# BUS_SPLIT_DISPLAY_1.net
KiCad netlist of a schematic drawn in EAGLE
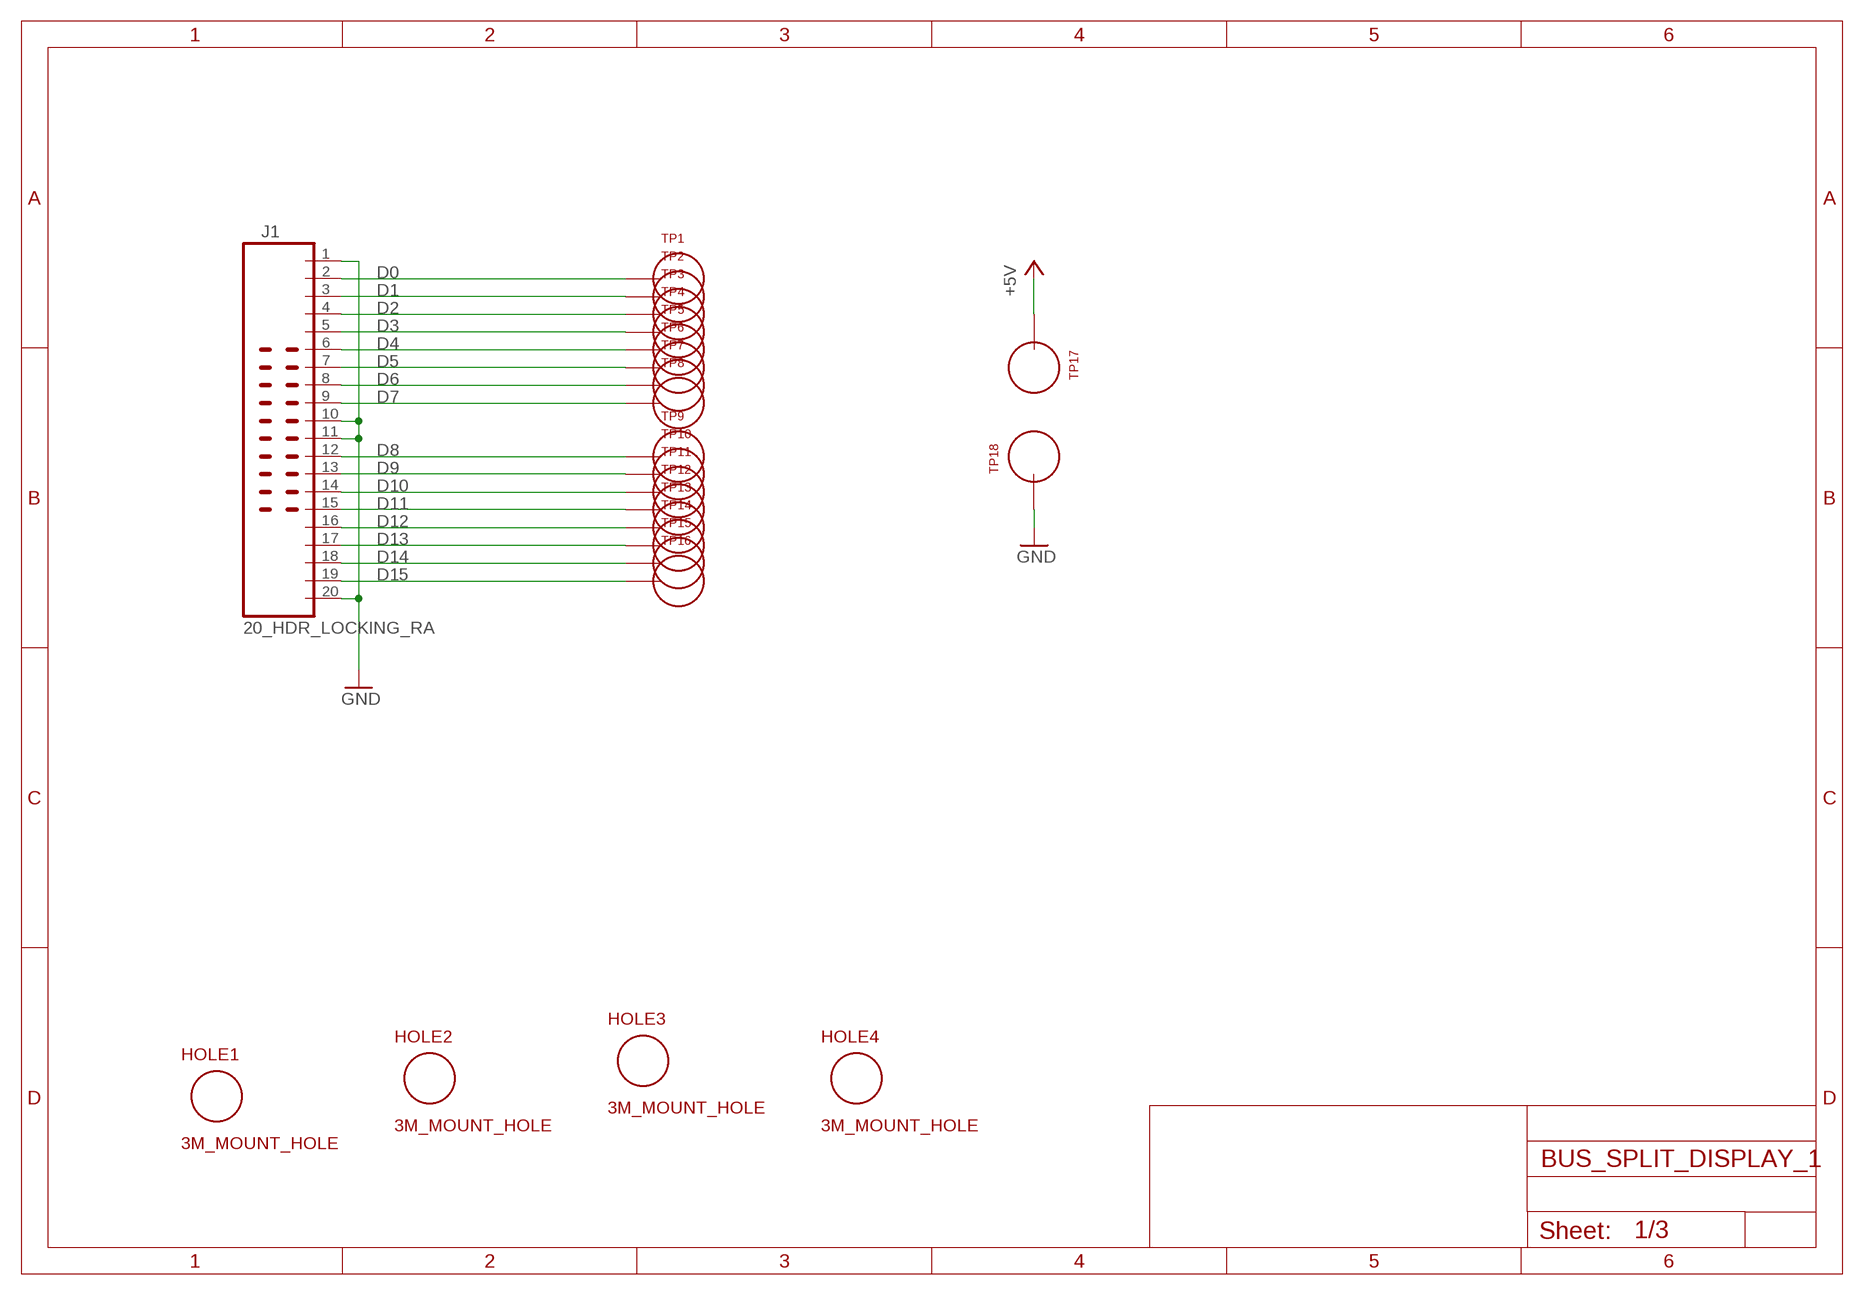
[diagram p0: schematic, sheet 1]
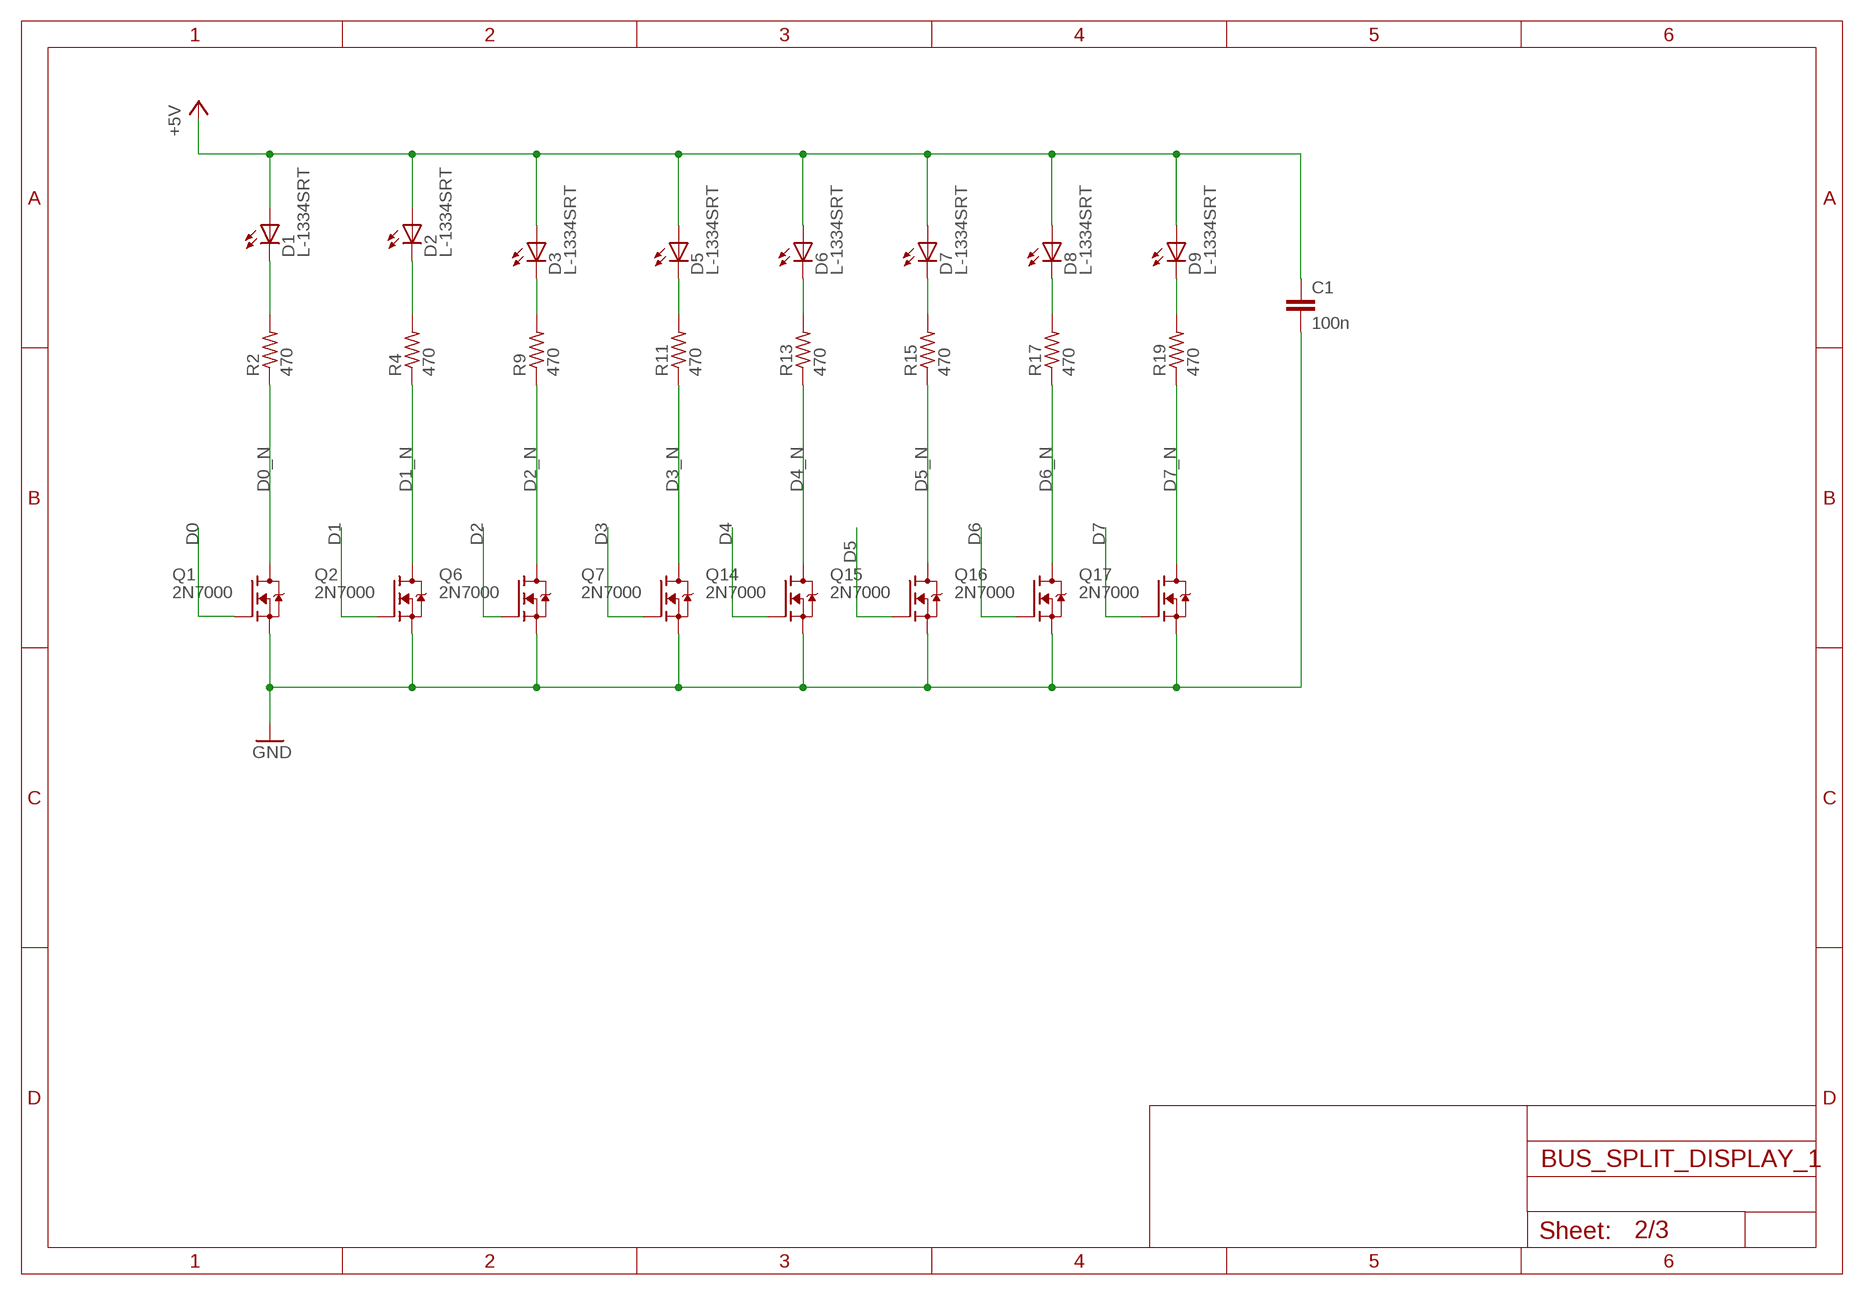
[diagram p1: schematic, sheet 2]
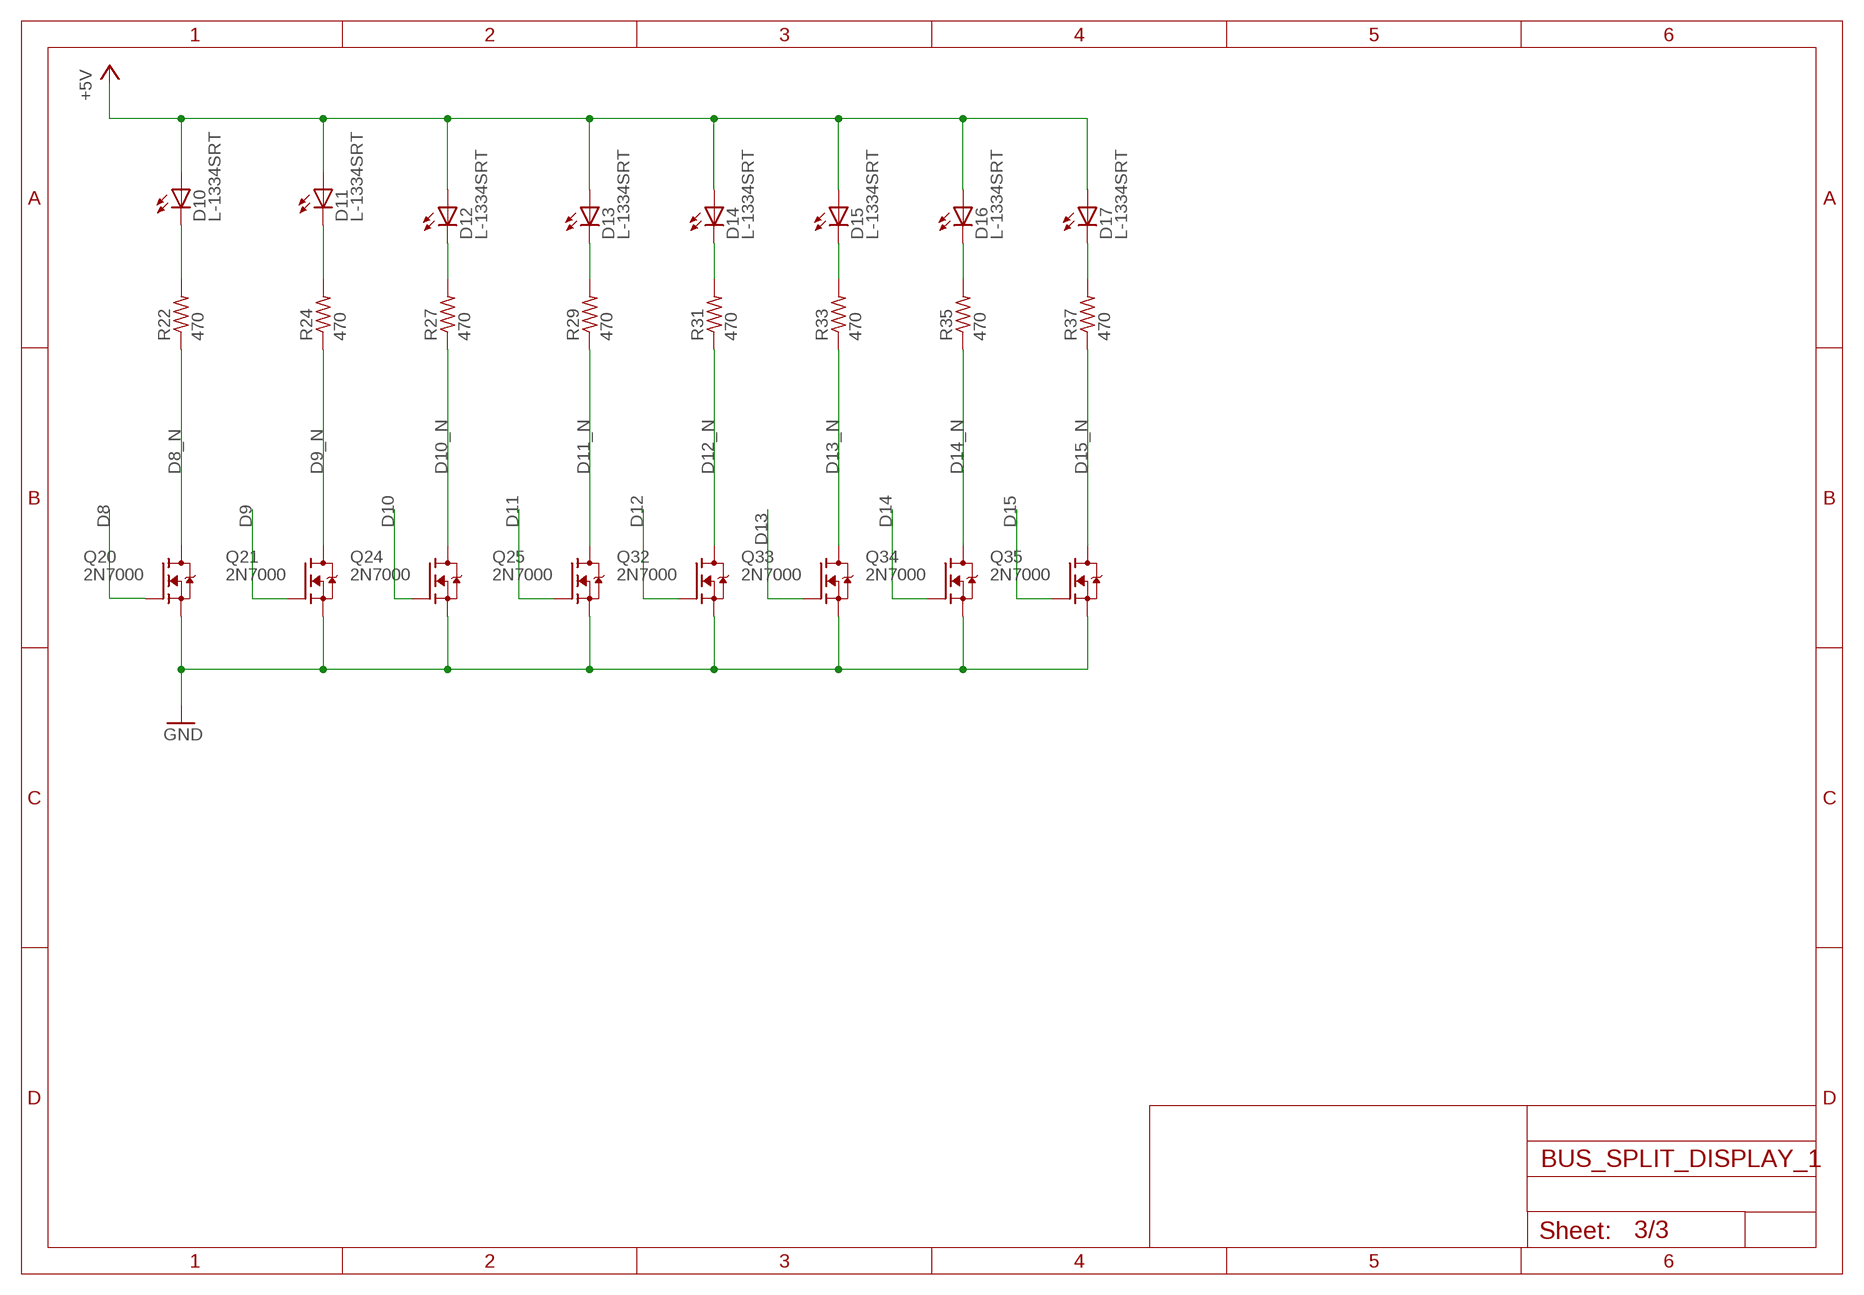
[diagram p2: schematic, sheet 3]

(export (version "E")
  (design (tool "Eeschema 10.0.6"))
  (components
    (comp (ref "D10")
      (value "L-1334SRT")
      (footprint "eagle-import:LED3MM")
      (libsource (lib "eagle-import") (part "L-1334SRT"))
    )
    (comp (ref "D11")
      (value "L-1334SRT")
      (footprint "eagle-import:LED3MM")
      (libsource (lib "eagle-import") (part "L-1334SRT"))
    )
    (comp (ref "D12")
      (value "L-1334SRT")
      (footprint "eagle-import:LED3MM")
      (libsource (lib "eagle-import") (part "L-1334SRT"))
    )
    (comp (ref "D13")
      (value "L-1334SRT")
      (footprint "eagle-import:LED3MM")
      (libsource (lib "eagle-import") (part "L-1334SRT"))
    )
    (comp (ref "D14")
      (value "L-1334SRT")
      (footprint "eagle-import:LED3MM")
      (libsource (lib "eagle-import") (part "L-1334SRT"))
    )
    (comp (ref "D15")
      (value "L-1334SRT")
      (footprint "eagle-import:LED3MM")
      (libsource (lib "eagle-import") (part "L-1334SRT"))
    )
    (comp (ref "D16")
      (value "L-1334SRT")
      (footprint "eagle-import:LED3MM")
      (libsource (lib "eagle-import") (part "L-1334SRT"))
    )
    (comp (ref "D17")
      (value "L-1334SRT")
      (footprint "eagle-import:LED3MM")
      (libsource (lib "eagle-import") (part "L-1334SRT"))
    )
    (comp (ref "Q20")
      (value "2N7000")
      (footprint "eagle-import:TO92-DGS")
      (libsource (lib "eagle-import") (part "2N7000"))
    )
    (comp (ref "Q21")
      (value "2N7000")
      (footprint "eagle-import:TO92-DGS")
      (libsource (lib "eagle-import") (part "2N7000"))
    )
    (comp (ref "Q24")
      (value "2N7000")
      (footprint "eagle-import:TO92-DGS")
      (libsource (lib "eagle-import") (part "2N7000"))
    )
    (comp (ref "Q25")
      (value "2N7000")
      (footprint "eagle-import:TO92-DGS")
      (libsource (lib "eagle-import") (part "2N7000"))
    )
    (comp (ref "Q32")
      (value "2N7000")
      (footprint "eagle-import:TO92-DGS")
      (libsource (lib "eagle-import") (part "2N7000"))
    )
    (comp (ref "Q33")
      (value "2N7000")
      (footprint "eagle-import:TO92-DGS")
      (libsource (lib "eagle-import") (part "2N7000"))
    )
    (comp (ref "Q34")
      (value "2N7000")
      (footprint "eagle-import:TO92-DGS")
      (libsource (lib "eagle-import") (part "2N7000"))
    )
    (comp (ref "Q35")
      (value "2N7000")
      (footprint "eagle-import:TO92-DGS")
      (libsource (lib "eagle-import") (part "2N7000"))
    )
    (comp (ref "R22")
      (value "470")
      (footprint "eagle-import:R_P2INCH")
      (libsource (lib "eagle-import") (part "R_P2INCH"))
    )
    (comp (ref "R24")
      (value "470")
      (footprint "eagle-import:R_P2INCH")
      (libsource (lib "eagle-import") (part "R_P2INCH"))
    )
    (comp (ref "R27")
      (value "470")
      (footprint "eagle-import:R_P2INCH")
      (libsource (lib "eagle-import") (part "R_P2INCH"))
    )
    (comp (ref "R29")
      (value "470")
      (footprint "eagle-import:R_P2INCH")
      (libsource (lib "eagle-import") (part "R_P2INCH"))
    )
    (comp (ref "R31")
      (value "470")
      (footprint "eagle-import:R_P2INCH")
      (libsource (lib "eagle-import") (part "R_P2INCH"))
    )
    (comp (ref "R33")
      (value "470")
      (footprint "eagle-import:R_P2INCH")
      (libsource (lib "eagle-import") (part "R_P2INCH"))
    )
    (comp (ref "R35")
      (value "470")
      (footprint "eagle-import:R_P2INCH")
      (libsource (lib "eagle-import") (part "R_P2INCH"))
    )
    (comp (ref "R37")
      (value "470")
      (footprint "eagle-import:R_P2INCH")
      (libsource (lib "eagle-import") (part "R_P2INCH"))
    )
    (comp (ref "HOLE1")
      (value "3M_MOUNT_HOLE")
      (footprint "eagle-import:3M_HOLE")
      (libsource (lib "eagle-import") (part "3M_MOUNT_HOLE"))
    )
    (comp (ref "HOLE2")
      (value "3M_MOUNT_HOLE")
      (footprint "eagle-import:3M_HOLE")
      (libsource (lib "eagle-import") (part "3M_MOUNT_HOLE"))
    )
    (comp (ref "HOLE3")
      (value "3M_MOUNT_HOLE")
      (footprint "eagle-import:3M_HOLE")
      (libsource (lib "eagle-import") (part "3M_MOUNT_HOLE"))
    )
    (comp (ref "HOLE4")
      (value "3M_MOUNT_HOLE")
      (footprint "eagle-import:3M_HOLE")
      (libsource (lib "eagle-import") (part "3M_MOUNT_HOLE"))
    )
    (comp (ref "J1")
      (value "20_HDR_LOCKING_RA")
      (footprint "eagle-import:20_HDR_LOCKING_RA")
      (libsource (lib "eagle-import") (part "20_HDR_LOCKING_RA"))
    )
    (comp (ref "TP1")
      (value "TEST_LOOP")
      (footprint "eagle-import:TEST_LOOP")
      (libsource (lib "eagle-import") (part "TEST_LOOP"))
    )
    (comp (ref "TP2")
      (value "TEST_LOOP")
      (footprint "eagle-import:TEST_LOOP")
      (libsource (lib "eagle-import") (part "TEST_LOOP"))
    )
    (comp (ref "TP3")
      (value "TEST_LOOP")
      (footprint "eagle-import:TEST_LOOP")
      (libsource (lib "eagle-import") (part "TEST_LOOP"))
    )
    (comp (ref "TP4")
      (value "TEST_LOOP")
      (footprint "eagle-import:TEST_LOOP")
      (libsource (lib "eagle-import") (part "TEST_LOOP"))
    )
    (comp (ref "TP5")
      (value "TEST_LOOP")
      (footprint "eagle-import:TEST_LOOP")
      (libsource (lib "eagle-import") (part "TEST_LOOP"))
    )
    (comp (ref "TP6")
      (value "TEST_LOOP")
      (footprint "eagle-import:TEST_LOOP")
      (libsource (lib "eagle-import") (part "TEST_LOOP"))
    )
    (comp (ref "TP7")
      (value "TEST_LOOP")
      (footprint "eagle-import:TEST_LOOP")
      (libsource (lib "eagle-import") (part "TEST_LOOP"))
    )
    (comp (ref "TP8")
      (value "TEST_LOOP")
      (footprint "eagle-import:TEST_LOOP")
      (libsource (lib "eagle-import") (part "TEST_LOOP"))
    )
    (comp (ref "TP9")
      (value "TEST_LOOP")
      (footprint "eagle-import:TEST_LOOP")
      (libsource (lib "eagle-import") (part "TEST_LOOP"))
    )
    (comp (ref "TP10")
      (value "TEST_LOOP")
      (footprint "eagle-import:TEST_LOOP")
      (libsource (lib "eagle-import") (part "TEST_LOOP"))
    )
    (comp (ref "TP11")
      (value "TEST_LOOP")
      (footprint "eagle-import:TEST_LOOP")
      (libsource (lib "eagle-import") (part "TEST_LOOP"))
    )
    (comp (ref "TP12")
      (value "TEST_LOOP")
      (footprint "eagle-import:TEST_LOOP")
      (libsource (lib "eagle-import") (part "TEST_LOOP"))
    )
    (comp (ref "TP13")
      (value "TEST_LOOP")
      (footprint "eagle-import:TEST_LOOP")
      (libsource (lib "eagle-import") (part "TEST_LOOP"))
    )
    (comp (ref "TP14")
      (value "TEST_LOOP")
      (footprint "eagle-import:TEST_LOOP")
      (libsource (lib "eagle-import") (part "TEST_LOOP"))
    )
    (comp (ref "TP15")
      (value "TEST_LOOP")
      (footprint "eagle-import:TEST_LOOP")
      (libsource (lib "eagle-import") (part "TEST_LOOP"))
    )
    (comp (ref "TP16")
      (value "TEST_LOOP")
      (footprint "eagle-import:TEST_LOOP")
      (libsource (lib "eagle-import") (part "TEST_LOOP"))
    )
    (comp (ref "TP17")
      (value "TEST_LOOP")
      (footprint "eagle-import:TEST_LOOP")
      (libsource (lib "eagle-import") (part "TEST_LOOP"))
    )
    (comp (ref "TP18")
      (value "TEST_LOOP")
      (footprint "eagle-import:TEST_LOOP")
      (libsource (lib "eagle-import") (part "TEST_LOOP"))
    )
    (comp (ref "C1")
      (value "100n")
      (footprint "eagle-import:CAP_P2INCH")
      (libsource (lib "eagle-import") (part "C_P2INCH"))
    )
    (comp (ref "D1")
      (value "L-1334SRT")
      (footprint "eagle-import:LED3MM")
      (libsource (lib "eagle-import") (part "L-1334SRT"))
    )
    (comp (ref "D2")
      (value "L-1334SRT")
      (footprint "eagle-import:LED3MM")
      (libsource (lib "eagle-import") (part "L-1334SRT"))
    )
    (comp (ref "D3")
      (value "L-1334SRT")
      (footprint "eagle-import:LED3MM")
      (libsource (lib "eagle-import") (part "L-1334SRT"))
    )
    (comp (ref "D5")
      (value "L-1334SRT")
      (footprint "eagle-import:LED3MM")
      (libsource (lib "eagle-import") (part "L-1334SRT"))
    )
    (comp (ref "D6")
      (value "L-1334SRT")
      (footprint "eagle-import:LED3MM")
      (libsource (lib "eagle-import") (part "L-1334SRT"))
    )
    (comp (ref "D7")
      (value "L-1334SRT")
      (footprint "eagle-import:LED3MM")
      (libsource (lib "eagle-import") (part "L-1334SRT"))
    )
    (comp (ref "D8")
      (value "L-1334SRT")
      (footprint "eagle-import:LED3MM")
      (libsource (lib "eagle-import") (part "L-1334SRT"))
    )
    (comp (ref "D9")
      (value "L-1334SRT")
      (footprint "eagle-import:LED3MM")
      (libsource (lib "eagle-import") (part "L-1334SRT"))
    )
    (comp (ref "Q1")
      (value "2N7000")
      (footprint "eagle-import:TO92-DGS")
      (libsource (lib "eagle-import") (part "2N7000"))
    )
    (comp (ref "Q2")
      (value "2N7000")
      (footprint "eagle-import:TO92-DGS")
      (libsource (lib "eagle-import") (part "2N7000"))
    )
    (comp (ref "Q6")
      (value "2N7000")
      (footprint "eagle-import:TO92-DGS")
      (libsource (lib "eagle-import") (part "2N7000"))
    )
    (comp (ref "Q7")
      (value "2N7000")
      (footprint "eagle-import:TO92-DGS")
      (libsource (lib "eagle-import") (part "2N7000"))
    )
    (comp (ref "Q14")
      (value "2N7000")
      (footprint "eagle-import:TO92-DGS")
      (libsource (lib "eagle-import") (part "2N7000"))
    )
    (comp (ref "Q15")
      (value "2N7000")
      (footprint "eagle-import:TO92-DGS")
      (libsource (lib "eagle-import") (part "2N7000"))
    )
    (comp (ref "Q16")
      (value "2N7000")
      (footprint "eagle-import:TO92-DGS")
      (libsource (lib "eagle-import") (part "2N7000"))
    )
    (comp (ref "Q17")
      (value "2N7000")
      (footprint "eagle-import:TO92-DGS")
      (libsource (lib "eagle-import") (part "2N7000"))
    )
    (comp (ref "R2")
      (value "470")
      (footprint "eagle-import:R_P2INCH")
      (libsource (lib "eagle-import") (part "R_P2INCH"))
    )
    (comp (ref "R4")
      (value "470")
      (footprint "eagle-import:R_P2INCH")
      (libsource (lib "eagle-import") (part "R_P2INCH"))
    )
    (comp (ref "R9")
      (value "470")
      (footprint "eagle-import:R_P2INCH")
      (libsource (lib "eagle-import") (part "R_P2INCH"))
    )
    (comp (ref "R11")
      (value "470")
      (footprint "eagle-import:R_P2INCH")
      (libsource (lib "eagle-import") (part "R_P2INCH"))
    )
    (comp (ref "R13")
      (value "470")
      (footprint "eagle-import:R_P2INCH")
      (libsource (lib "eagle-import") (part "R_P2INCH"))
    )
    (comp (ref "R15")
      (value "470")
      (footprint "eagle-import:R_P2INCH")
      (libsource (lib "eagle-import") (part "R_P2INCH"))
    )
    (comp (ref "R17")
      (value "470")
      (footprint "eagle-import:R_P2INCH")
      (libsource (lib "eagle-import") (part "R_P2INCH"))
    )
    (comp (ref "R19")
      (value "470")
      (footprint "eagle-import:R_P2INCH")
      (libsource (lib "eagle-import") (part "R_P2INCH"))
    )
  )
  (nets
    (net (code "1") (name "+5V") (class "Default")
      (node (ref "C1") (pin "1") (pinfunction "1_1") (pintype "passive"))
      (node (ref "D1") (pin "A") (pinfunction "A_A") (pintype "passive"))
      (node (ref "D10") (pin "A") (pinfunction "A_A") (pintype "passive"))
      (node (ref "D11") (pin "A") (pinfunction "A_A") (pintype "passive"))
      (node (ref "D12") (pin "A") (pinfunction "A_A") (pintype "passive"))
      (node (ref "D13") (pin "A") (pinfunction "A_A") (pintype "passive"))
      (node (ref "D14") (pin "A") (pinfunction "A_A") (pintype "passive"))
      (node (ref "D15") (pin "A") (pinfunction "A_A") (pintype "passive"))
      (node (ref "D16") (pin "A") (pinfunction "A_A") (pintype "passive"))
      (node (ref "D17") (pin "A") (pinfunction "A_A") (pintype "passive"))
      (node (ref "D2") (pin "A") (pinfunction "A_A") (pintype "passive"))
      (node (ref "D3") (pin "A") (pinfunction "A_A") (pintype "passive"))
      (node (ref "D5") (pin "A") (pinfunction "A_A") (pintype "passive"))
      (node (ref "D6") (pin "A") (pinfunction "A_A") (pintype "passive"))
      (node (ref "D7") (pin "A") (pinfunction "A_A") (pintype "passive"))
      (node (ref "D8") (pin "A") (pinfunction "A_A") (pintype "passive"))
      (node (ref "D9") (pin "A") (pinfunction "A_A") (pintype "passive"))
      (node (ref "TP17") (pin "P$1") (pinfunction "P$1_P$1") (pintype "bidirectional"))
    )
    (net (code "2") (name "D0") (class "Default")
      (node (ref "J1") (pin "2") (pinfunction "2_2") (pintype "bidirectional"))
      (node (ref "Q1") (pin "G") (pinfunction "G_G") (pintype "passive"))
      (node (ref "TP1") (pin "P$1") (pinfunction "P$1_P$1") (pintype "bidirectional"))
    )
    (net (code "3") (name "D0_N") (class "Default")
      (node (ref "Q1") (pin "D") (pinfunction "D_D") (pintype "passive"))
      (node (ref "R2") (pin "1") (pinfunction "1_1") (pintype "passive"))
    )
    (net (code "4") (name "D1") (class "Default")
      (node (ref "J1") (pin "3") (pinfunction "3_3") (pintype "bidirectional"))
      (node (ref "Q2") (pin "G") (pinfunction "G_G") (pintype "passive"))
      (node (ref "TP2") (pin "P$1") (pinfunction "P$1_P$1") (pintype "bidirectional"))
    )
    (net (code "5") (name "D1_N") (class "Default")
      (node (ref "Q2") (pin "D") (pinfunction "D_D") (pintype "passive"))
      (node (ref "R4") (pin "1") (pinfunction "1_1") (pintype "passive"))
    )
    (net (code "6") (name "D2") (class "Default")
      (node (ref "J1") (pin "4") (pinfunction "4_4") (pintype "bidirectional"))
      (node (ref "Q6") (pin "G") (pinfunction "G_G") (pintype "passive"))
      (node (ref "TP3") (pin "P$1") (pinfunction "P$1_P$1") (pintype "bidirectional"))
    )
    (net (code "7") (name "D2_N") (class "Default")
      (node (ref "Q6") (pin "D") (pinfunction "D_D") (pintype "passive"))
      (node (ref "R9") (pin "1") (pinfunction "1_1") (pintype "passive"))
    )
    (net (code "8") (name "D3") (class "Default")
      (node (ref "J1") (pin "5") (pinfunction "5_5") (pintype "bidirectional"))
      (node (ref "Q7") (pin "G") (pinfunction "G_G") (pintype "passive"))
      (node (ref "TP4") (pin "P$1") (pinfunction "P$1_P$1") (pintype "bidirectional"))
    )
    (net (code "9") (name "D3_N") (class "Default")
      (node (ref "Q7") (pin "D") (pinfunction "D_D") (pintype "passive"))
      (node (ref "R11") (pin "1") (pinfunction "1_1") (pintype "passive"))
    )
    (net (code "10") (name "D4") (class "Default")
      (node (ref "J1") (pin "6") (pinfunction "6_6") (pintype "bidirectional"))
      (node (ref "Q14") (pin "G") (pinfunction "G_G") (pintype "passive"))
      (node (ref "TP5") (pin "P$1") (pinfunction "P$1_P$1") (pintype "bidirectional"))
    )
    (net (code "11") (name "D4_N") (class "Default")
      (node (ref "Q14") (pin "D") (pinfunction "D_D") (pintype "passive"))
      (node (ref "R13") (pin "1") (pinfunction "1_1") (pintype "passive"))
    )
    (net (code "12") (name "D5") (class "Default")
      (node (ref "J1") (pin "7") (pinfunction "7_7") (pintype "bidirectional"))
      (node (ref "Q15") (pin "G") (pinfunction "G_G") (pintype "passive"))
      (node (ref "TP6") (pin "P$1") (pinfunction "P$1_P$1") (pintype "bidirectional"))
    )
    (net (code "13") (name "D5_N") (class "Default")
      (node (ref "Q15") (pin "D") (pinfunction "D_D") (pintype "passive"))
      (node (ref "R15") (pin "1") (pinfunction "1_1") (pintype "passive"))
    )
    (net (code "14") (name "D6") (class "Default")
      (node (ref "J1") (pin "8") (pinfunction "8_8") (pintype "bidirectional"))
      (node (ref "Q16") (pin "G") (pinfunction "G_G") (pintype "passive"))
      (node (ref "TP7") (pin "P$1") (pinfunction "P$1_P$1") (pintype "bidirectional"))
    )
    (net (code "15") (name "D6_N") (class "Default")
      (node (ref "Q16") (pin "D") (pinfunction "D_D") (pintype "passive"))
      (node (ref "R17") (pin "1") (pinfunction "1_1") (pintype "passive"))
    )
    (net (code "16") (name "D7") (class "Default")
      (node (ref "J1") (pin "9") (pinfunction "9_9") (pintype "bidirectional"))
      (node (ref "Q17") (pin "G") (pinfunction "G_G") (pintype "passive"))
      (node (ref "TP8") (pin "P$1") (pinfunction "P$1_P$1") (pintype "bidirectional"))
    )
    (net (code "17") (name "D7_N") (class "Default")
      (node (ref "Q17") (pin "D") (pinfunction "D_D") (pintype "passive"))
      (node (ref "R19") (pin "1") (pinfunction "1_1") (pintype "passive"))
    )
    (net (code "18") (name "D8") (class "Default")
      (node (ref "J1") (pin "12") (pinfunction "12_12") (pintype "bidirectional"))
      (node (ref "Q20") (pin "G") (pinfunction "G_G") (pintype "passive"))
      (node (ref "TP9") (pin "P$1") (pinfunction "P$1_P$1") (pintype "bidirectional"))
    )
    (net (code "19") (name "D8_N") (class "Default")
      (node (ref "Q20") (pin "D") (pinfunction "D_D") (pintype "passive"))
      (node (ref "R22") (pin "1") (pinfunction "1_1") (pintype "passive"))
    )
    (net (code "20") (name "D9") (class "Default")
      (node (ref "J1") (pin "13") (pinfunction "13_13") (pintype "bidirectional"))
      (node (ref "Q21") (pin "G") (pinfunction "G_G") (pintype "passive"))
      (node (ref "TP10") (pin "P$1") (pinfunction "P$1_P$1") (pintype "bidirectional"))
    )
    (net (code "21") (name "D9_N") (class "Default")
      (node (ref "Q21") (pin "D") (pinfunction "D_D") (pintype "passive"))
      (node (ref "R24") (pin "1") (pinfunction "1_1") (pintype "passive"))
    )
    (net (code "22") (name "D10") (class "Default")
      (node (ref "J1") (pin "14") (pinfunction "14_14") (pintype "bidirectional"))
      (node (ref "Q24") (pin "G") (pinfunction "G_G") (pintype "passive"))
      (node (ref "TP11") (pin "P$1") (pinfunction "P$1_P$1") (pintype "bidirectional"))
    )
    (net (code "23") (name "D10_N") (class "Default")
      (node (ref "Q24") (pin "D") (pinfunction "D_D") (pintype "passive"))
      (node (ref "R27") (pin "1") (pinfunction "1_1") (pintype "passive"))
    )
    (net (code "24") (name "D11") (class "Default")
      (node (ref "J1") (pin "15") (pinfunction "15_15") (pintype "bidirectional"))
      (node (ref "Q25") (pin "G") (pinfunction "G_G") (pintype "passive"))
      (node (ref "TP12") (pin "P$1") (pinfunction "P$1_P$1") (pintype "bidirectional"))
    )
    (net (code "25") (name "D11_N") (class "Default")
      (node (ref "Q25") (pin "D") (pinfunction "D_D") (pintype "passive"))
      (node (ref "R29") (pin "1") (pinfunction "1_1") (pintype "passive"))
    )
    (net (code "26") (name "D12") (class "Default")
      (node (ref "J1") (pin "16") (pinfunction "16_16") (pintype "bidirectional"))
      (node (ref "Q32") (pin "G") (pinfunction "G_G") (pintype "passive"))
      (node (ref "TP13") (pin "P$1") (pinfunction "P$1_P$1") (pintype "bidirectional"))
    )
    (net (code "27") (name "D12_N") (class "Default")
      (node (ref "Q32") (pin "D") (pinfunction "D_D") (pintype "passive"))
      (node (ref "R31") (pin "1") (pinfunction "1_1") (pintype "passive"))
    )
    (net (code "28") (name "D13") (class "Default")
      (node (ref "J1") (pin "17") (pinfunction "17_17") (pintype "bidirectional"))
      (node (ref "Q33") (pin "G") (pinfunction "G_G") (pintype "passive"))
      (node (ref "TP14") (pin "P$1") (pinfunction "P$1_P$1") (pintype "bidirectional"))
    )
    (net (code "29") (name "D13_N") (class "Default")
      (node (ref "Q33") (pin "D") (pinfunction "D_D") (pintype "passive"))
      (node (ref "R33") (pin "1") (pinfunction "1_1") (pintype "passive"))
    )
    (net (code "30") (name "D14") (class "Default")
      (node (ref "J1") (pin "18") (pinfunction "18_18") (pintype "bidirectional"))
      (node (ref "Q34") (pin "G") (pinfunction "G_G") (pintype "passive"))
      (node (ref "TP15") (pin "P$1") (pinfunction "P$1_P$1") (pintype "bidirectional"))
    )
    (net (code "31") (name "D14_N") (class "Default")
      (node (ref "Q34") (pin "D") (pinfunction "D_D") (pintype "passive"))
      (node (ref "R35") (pin "1") (pinfunction "1_1") (pintype "passive"))
    )
    (net (code "32") (name "D15") (class "Default")
      (node (ref "J1") (pin "19") (pinfunction "19_19") (pintype "bidirectional"))
      (node (ref "Q35") (pin "G") (pinfunction "G_G") (pintype "passive"))
      (node (ref "TP16") (pin "P$1") (pinfunction "P$1_P$1") (pintype "bidirectional"))
    )
    (net (code "33") (name "D15_N") (class "Default")
      (node (ref "Q35") (pin "D") (pinfunction "D_D") (pintype "passive"))
      (node (ref "R37") (pin "1") (pinfunction "1_1") (pintype "passive"))
    )
    (net (code "34") (name "GND") (class "Default")
      (node (ref "C1") (pin "2") (pinfunction "2_2") (pintype "passive"))
      (node (ref "J1") (pin "1") (pinfunction "1_1") (pintype "bidirectional"))
      (node (ref "J1") (pin "10") (pinfunction "10_10") (pintype "bidirectional"))
      (node (ref "J1") (pin "11") (pinfunction "11_11") (pintype "bidirectional"))
      (node (ref "J1") (pin "20") (pinfunction "20_20") (pintype "bidirectional"))
      (node (ref "Q1") (pin "S") (pinfunction "S_S") (pintype "passive"))
      (node (ref "Q14") (pin "S") (pinfunction "S_S") (pintype "passive"))
      (node (ref "Q15") (pin "S") (pinfunction "S_S") (pintype "passive"))
      (node (ref "Q16") (pin "S") (pinfunction "S_S") (pintype "passive"))
      (node (ref "Q17") (pin "S") (pinfunction "S_S") (pintype "passive"))
      (node (ref "Q2") (pin "S") (pinfunction "S_S") (pintype "passive"))
      (node (ref "Q20") (pin "S") (pinfunction "S_S") (pintype "passive"))
      (node (ref "Q21") (pin "S") (pinfunction "S_S") (pintype "passive"))
      (node (ref "Q24") (pin "S") (pinfunction "S_S") (pintype "passive"))
      (node (ref "Q25") (pin "S") (pinfunction "S_S") (pintype "passive"))
      (node (ref "Q32") (pin "S") (pinfunction "S_S") (pintype "passive"))
      (node (ref "Q33") (pin "S") (pinfunction "S_S") (pintype "passive"))
      (node (ref "Q34") (pin "S") (pinfunction "S_S") (pintype "passive"))
      (node (ref "Q35") (pin "S") (pinfunction "S_S") (pintype "passive"))
      (node (ref "Q6") (pin "S") (pinfunction "S_S") (pintype "passive"))
      (node (ref "Q7") (pin "S") (pinfunction "S_S") (pintype "passive"))
      (node (ref "TP18") (pin "P$1") (pinfunction "P$1_P$1") (pintype "bidirectional"))
    )
    (net (code "35") (name "Net-(D1-C)") (class "Default")
      (node (ref "D1") (pin "K") (pinfunction "C_K") (pintype "passive"))
      (node (ref "R2") (pin "2") (pinfunction "2_2") (pintype "passive"))
    )
    (net (code "36") (name "Net-(D2-C)") (class "Default")
      (node (ref "D2") (pin "K") (pinfunction "C_K") (pintype "passive"))
      (node (ref "R4") (pin "2") (pinfunction "2_2") (pintype "passive"))
    )
    (net (code "37") (name "Net-(D3-C)") (class "Default")
      (node (ref "D3") (pin "K") (pinfunction "C_K") (pintype "passive"))
      (node (ref "R9") (pin "2") (pinfunction "2_2") (pintype "passive"))
    )
    (net (code "38") (name "Net-(D5-C)") (class "Default")
      (node (ref "D5") (pin "K") (pinfunction "C_K") (pintype "passive"))
      (node (ref "R11") (pin "2") (pinfunction "2_2") (pintype "passive"))
    )
    (net (code "39") (name "Net-(D6-C)") (class "Default")
      (node (ref "D6") (pin "K") (pinfunction "C_K") (pintype "passive"))
      (node (ref "R13") (pin "2") (pinfunction "2_2") (pintype "passive"))
    )
    (net (code "40") (name "Net-(D7-C)") (class "Default")
      (node (ref "D7") (pin "K") (pinfunction "C_K") (pintype "passive"))
      (node (ref "R15") (pin "2") (pinfunction "2_2") (pintype "passive"))
    )
    (net (code "41") (name "Net-(D8-C)") (class "Default")
      (node (ref "D8") (pin "K") (pinfunction "C_K") (pintype "passive"))
      (node (ref "R17") (pin "2") (pinfunction "2_2") (pintype "passive"))
    )
    (net (code "42") (name "Net-(D9-C)") (class "Default")
      (node (ref "D9") (pin "K") (pinfunction "C_K") (pintype "passive"))
      (node (ref "R19") (pin "2") (pinfunction "2_2") (pintype "passive"))
    )
    (net (code "43") (name "Net-(D10-C)") (class "Default")
      (node (ref "D10") (pin "K") (pinfunction "C_K") (pintype "passive"))
      (node (ref "R22") (pin "2") (pinfunction "2_2") (pintype "passive"))
    )
    (net (code "44") (name "Net-(D11-C)") (class "Default")
      (node (ref "D11") (pin "K") (pinfunction "C_K") (pintype "passive"))
      (node (ref "R24") (pin "2") (pinfunction "2_2") (pintype "passive"))
    )
    (net (code "45") (name "Net-(D12-C)") (class "Default")
      (node (ref "D12") (pin "K") (pinfunction "C_K") (pintype "passive"))
      (node (ref "R27") (pin "2") (pinfunction "2_2") (pintype "passive"))
    )
    (net (code "46") (name "Net-(D13-C)") (class "Default")
      (node (ref "D13") (pin "K") (pinfunction "C_K") (pintype "passive"))
      (node (ref "R29") (pin "2") (pinfunction "2_2") (pintype "passive"))
    )
    (net (code "47") (name "Net-(D14-C)") (class "Default")
      (node (ref "D14") (pin "K") (pinfunction "C_K") (pintype "passive"))
      (node (ref "R31") (pin "2") (pinfunction "2_2") (pintype "passive"))
    )
    (net (code "48") (name "Net-(D15-C)") (class "Default")
      (node (ref "D15") (pin "K") (pinfunction "C_K") (pintype "passive"))
      (node (ref "R33") (pin "2") (pinfunction "2_2") (pintype "passive"))
    )
    (net (code "49") (name "Net-(D16-C)") (class "Default")
      (node (ref "D16") (pin "K") (pinfunction "C_K") (pintype "passive"))
      (node (ref "R35") (pin "2") (pinfunction "2_2") (pintype "passive"))
    )
    (net (code "50") (name "Net-(D17-C)") (class "Default")
      (node (ref "D17") (pin "K") (pinfunction "C_K") (pintype "passive"))
      (node (ref "R37") (pin "2") (pinfunction "2_2") (pintype "passive"))
    )
  )
)
